# team.net
KiCad netlist of a schematic drawn in EAGLE
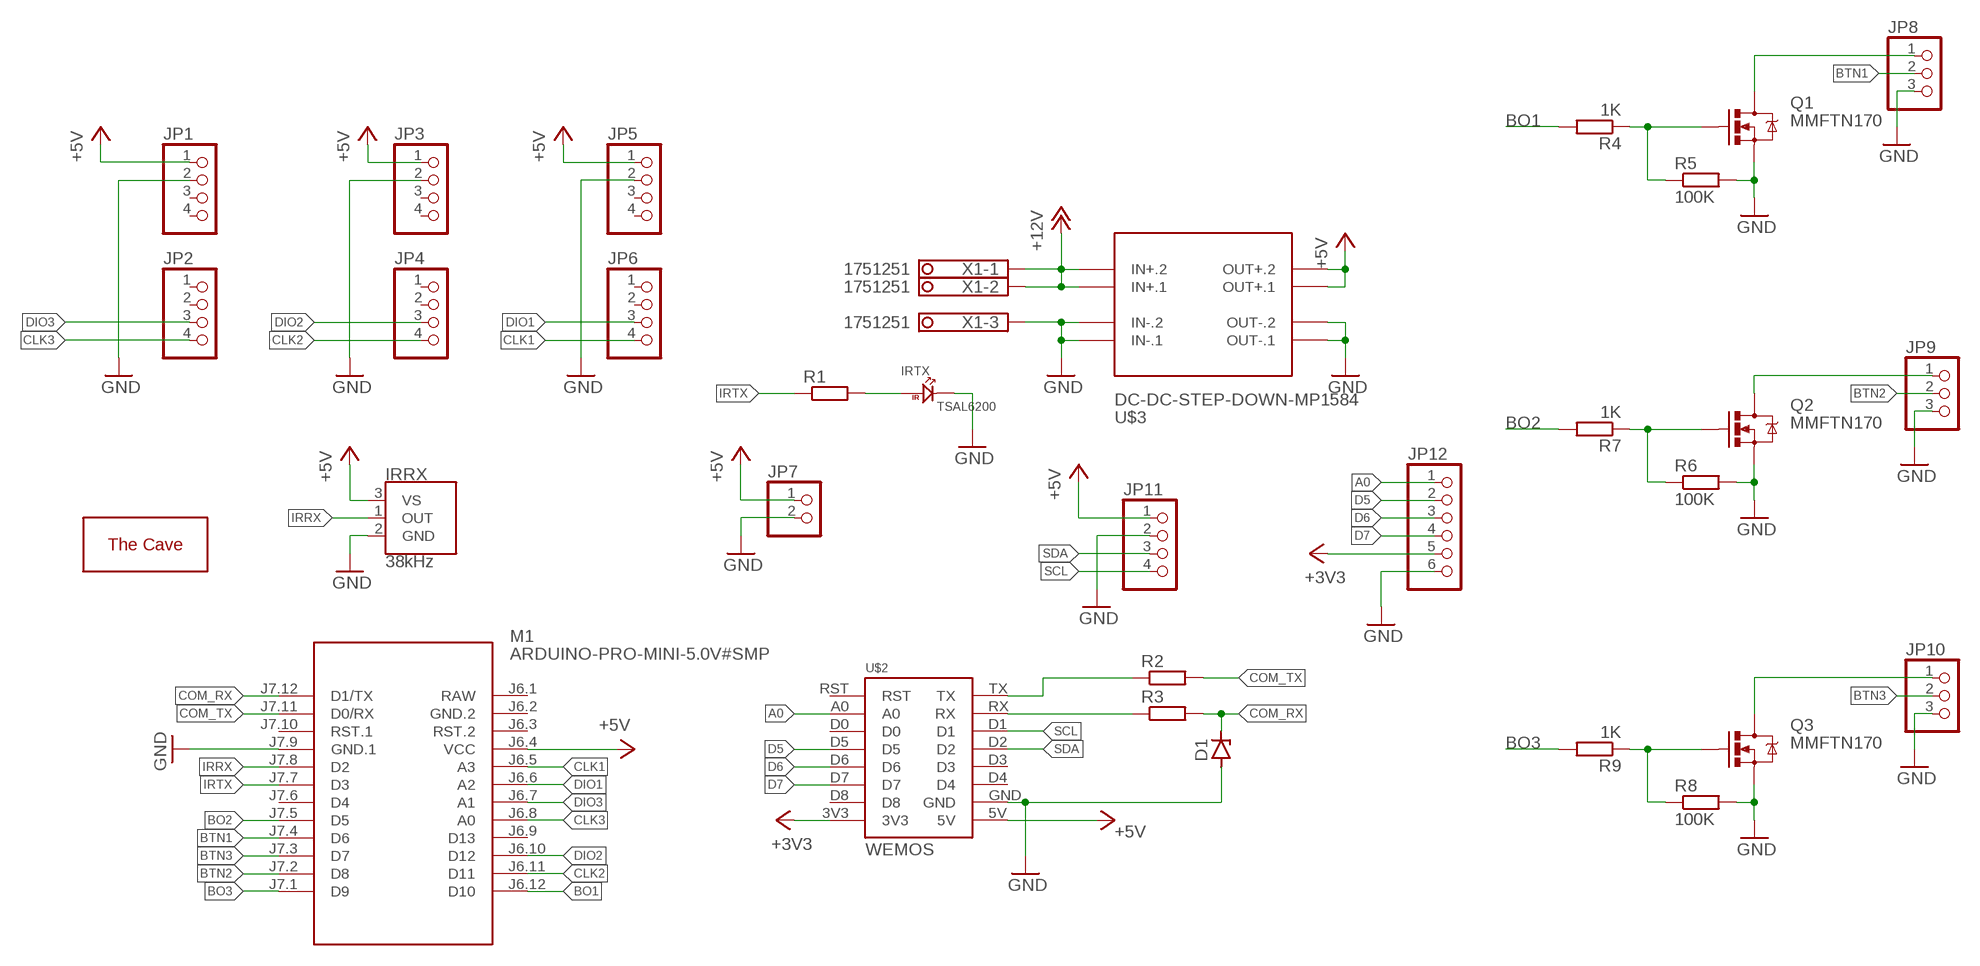
[diagram p0: schematic, sheet 1]

(export (version "E")
  (design (tool "Eeschema 10.0.6"))
  (components
    (comp (ref "D1")
      (value "ZENER-DIODEDO34-7")
      (footprint "eagle-import:DO34Z7")
      (libsource (lib "eagle-import") (part "ZENER-DIODEDO34-7"))
    )
    (comp (ref "IRRX")
      (value "38kHz")
      (footprint "eagle-import:TSOP382")
      (libsource (lib "eagle-import") (part "TSOP38238"))
    )
    (comp (ref "IRTX")
      (value "TSAL6200")
      (footprint "eagle-import:TSAL6200")
      (libsource (lib "eagle-import") (part "TSAL6200"))
    )
    (comp (ref "JP1")
      (value "PINHD-1X4")
      (footprint "eagle-import:1X04")
      (libsource (lib "eagle-import") (part "PINHD-1X4"))
    )
    (comp (ref "JP2")
      (value "PINHD-1X4")
      (footprint "eagle-import:1X04")
      (libsource (lib "eagle-import") (part "PINHD-1X4"))
    )
    (comp (ref "JP3")
      (value "PINHD-1X4")
      (footprint "eagle-import:1X04")
      (libsource (lib "eagle-import") (part "PINHD-1X4"))
    )
    (comp (ref "JP4")
      (value "PINHD-1X4")
      (footprint "eagle-import:1X04")
      (libsource (lib "eagle-import") (part "PINHD-1X4"))
    )
    (comp (ref "JP5")
      (value "PINHD-1X4")
      (footprint "eagle-import:1X04")
      (libsource (lib "eagle-import") (part "PINHD-1X4"))
    )
    (comp (ref "JP6")
      (value "PINHD-1X4")
      (footprint "eagle-import:1X04")
      (libsource (lib "eagle-import") (part "PINHD-1X4"))
    )
    (comp (ref "JP7")
      (value "PINHD-1X2")
      (footprint "eagle-import:1X02")
      (libsource (lib "eagle-import") (part "PINHD-1X2"))
    )
    (comp (ref "JP8")
      (value "PINHD-1X3")
      (footprint "eagle-import:1X03")
      (libsource (lib "eagle-import") (part "PINHD-1X3"))
    )
    (comp (ref "JP9")
      (value "PINHD-1X3")
      (footprint "eagle-import:1X03")
      (libsource (lib "eagle-import") (part "PINHD-1X3"))
    )
    (comp (ref "JP10")
      (value "PINHD-1X3")
      (footprint "eagle-import:1X03")
      (libsource (lib "eagle-import") (part "PINHD-1X3"))
    )
    (comp (ref "JP11")
      (value "PINHD-1X4")
      (footprint "eagle-import:1X04")
      (libsource (lib "eagle-import") (part "PINHD-1X4"))
    )
    (comp (ref "JP12")
      (value "PINHD-1X6")
      (footprint "eagle-import:1X06")
      (libsource (lib "eagle-import") (part "PINHD-1X6"))
    )
    (comp (ref "M1")
      (value "ARDUINO-PRO-MINI-5.0V#SMP")
      (footprint "eagle-import:ARDUINO-PRO-MINI#SMP")
      (libsource (lib "eagle-import") (part "ARDUINO-PRO-MINI-#SMP5.0V"))
    )
    (comp (ref "Q1")
      (value "MMFTN170")
      (footprint "eagle-import:SOT23-3")
      (libsource (lib "eagle-import") (part "MOSFET-NCHANNELAO3404A"))
    )
    (comp (ref "Q2")
      (value "MMFTN170")
      (footprint "eagle-import:SOT23-3")
      (libsource (lib "eagle-import") (part "MOSFET-NCHANNELAO3404A"))
    )
    (comp (ref "Q3")
      (value "MMFTN170")
      (footprint "eagle-import:SOT23-3")
      (libsource (lib "eagle-import") (part "MOSFET-NCHANNELAO3404A"))
    )
    (comp (ref "R1")
      (value "R-EU_0207/7")
      (footprint "eagle-import:0207_7")
      (libsource (lib "eagle-import") (part "rcl_334_R-EU_0207/7"))
    )
    (comp (ref "R2")
      (value "R-EU_0207/7")
      (footprint "eagle-import:0207_7")
      (libsource (lib "eagle-import") (part "rcl_334_R-EU_0207/7"))
    )
    (comp (ref "R3")
      (value "R-EU_0207/7")
      (footprint "eagle-import:0207_7")
      (libsource (lib "eagle-import") (part "rcl_334_R-EU_0207/7"))
    )
    (comp (ref "R4")
      (value "1K")
      (footprint "eagle-import:R0805")
      (libsource (lib "eagle-import") (part "R-EU_R0805"))
    )
    (comp (ref "R5")
      (value "100K")
      (footprint "eagle-import:R0805")
      (libsource (lib "eagle-import") (part "R-EU_R0805"))
    )
    (comp (ref "R6")
      (value "100K")
      (footprint "eagle-import:R0805")
      (libsource (lib "eagle-import") (part "R-EU_R0805"))
    )
    (comp (ref "R7")
      (value "1K")
      (footprint "eagle-import:R0805")
      (libsource (lib "eagle-import") (part "R-EU_R0805"))
    )
    (comp (ref "R8")
      (value "100K")
      (footprint "eagle-import:R0805")
      (libsource (lib "eagle-import") (part "R-EU_R0805"))
    )
    (comp (ref "R9")
      (value "1K")
      (footprint "eagle-import:R0805")
      (libsource (lib "eagle-import") (part "R-EU_R0805"))
    )
    (comp (ref "U$1")
      (value "THECAVE_LOGO_NEW_TOP")
      (footprint "eagle-import:NEW_LOGO_TOP")
      (libsource (lib "eagle-import") (part "THECAVE_LOGO_NEW_TOP"))
    )
    (comp (ref "U$2")
      (value "WEMOS")
      (footprint "eagle-import:WEMOS")
      (libsource (lib "eagle-import") (part "WEMOS"))
    )
    (comp (ref "U$3")
      (value "DC-DC-STEP-DOWN-MP1584")
      (footprint "eagle-import:DC-DC-STEP-DOWN-MP1584")
      (libsource (lib "eagle-import") (part "DC-DC-STEP-DOWN-MP1584"))
    )
    (comp (ref "X1")
      (value "1751251")
      (footprint "eagle-import:1751251")
      (libsource (lib "eagle-import") (part "1751251"))
    )
  )
  (nets
    (net (code "1") (name "+3V3") (class "Default")
      (node (ref "JP12") (pin "5") (pinfunction "5_5") (pintype "passive"))
      (node (ref "U$2") (pin "3V3") (pinfunction "3V3_3V3") (pintype "bidirectional"))
    )
    (net (code "2") (name "+5V") (class "Default")
      (node (ref "IRRX") (pin "3") (pinfunction "VS_3") (pintype "bidirectional"))
      (node (ref "JP1") (pin "1") (pinfunction "1_1") (pintype "passive"))
      (node (ref "JP11") (pin "1") (pinfunction "1_1") (pintype "passive"))
      (node (ref "JP3") (pin "1") (pinfunction "1_1") (pintype "passive"))
      (node (ref "JP5") (pin "1") (pinfunction "1_1") (pintype "passive"))
      (node (ref "JP7") (pin "1") (pinfunction "1_1") (pintype "passive"))
      (node (ref "M1") (pin "J6.4") (pinfunction "VCC_J6.4") (pintype "power_in"))
      (node (ref "U$2") (pin "5V") (pinfunction "5V_5V") (pintype "bidirectional"))
      (node (ref "U$3") (pin "OUT+.1") (pinfunction "OUT+.1_OUT+.1") (pintype "bidirectional"))
      (node (ref "U$3") (pin "OUT+.2") (pinfunction "OUT+.2_OUT+.2") (pintype "bidirectional"))
    )
    (net (code "3") (name "+12V") (class "Default")
      (node (ref "U$3") (pin "IN+.1") (pinfunction "IN+.1_IN+.1") (pintype "bidirectional"))
      (node (ref "U$3") (pin "IN+.2") (pinfunction "IN+.2_IN+.2") (pintype "bidirectional"))
      (node (ref "X1") (pin "1") (pinfunction "K_1") (pintype "passive"))
      (node (ref "X1") (pin "2") (pinfunction "K_2") (pintype "passive"))
    )
    (net (code "4") (name "/GND.2") (class "Default")
      (node (ref "M1") (pin "J6.2") (pinfunction "GND.2_J6.2") (pintype "power_in"))
    )
    (net (code "5") (name "/RAW") (class "Default")
      (node (ref "M1") (pin "J6.1") (pinfunction "RAW_J6.1") (pintype "power_in"))
    )
    (net (code "6") (name "A0") (class "Default")
      (node (ref "JP12") (pin "1") (pinfunction "1_1") (pintype "passive"))
      (node (ref "U$2") (pin "A0") (pinfunction "A0_A0") (pintype "bidirectional"))
    )
    (net (code "7") (name "BO1") (class "Default")
      (node (ref "M1") (pin "J6.12") (pinfunction "D10_J6.12") (pintype "bidirectional"))
      (node (ref "R4") (pin "2") (pinfunction "2_2") (pintype "passive"))
    )
    (net (code "8") (name "BO2") (class "Default")
      (node (ref "M1") (pin "J7.5") (pinfunction "D5_J7.5") (pintype "bidirectional"))
      (node (ref "R7") (pin "2") (pinfunction "2_2") (pintype "passive"))
    )
    (net (code "9") (name "BO3") (class "Default")
      (node (ref "M1") (pin "J7.1") (pinfunction "D9_J7.1") (pintype "bidirectional"))
      (node (ref "R9") (pin "2") (pinfunction "2_2") (pintype "passive"))
    )
    (net (code "10") (name "BTN1") (class "Default")
      (node (ref "JP8") (pin "2") (pinfunction "2_2") (pintype "passive"))
      (node (ref "M1") (pin "J7.4") (pinfunction "D6_J7.4") (pintype "bidirectional"))
    )
    (net (code "11") (name "BTN2") (class "Default")
      (node (ref "JP9") (pin "2") (pinfunction "2_2") (pintype "passive"))
      (node (ref "M1") (pin "J7.2") (pinfunction "D8_J7.2") (pintype "bidirectional"))
    )
    (net (code "12") (name "BTN3") (class "Default")
      (node (ref "JP10") (pin "2") (pinfunction "2_2") (pintype "passive"))
      (node (ref "M1") (pin "J7.3") (pinfunction "D7_J7.3") (pintype "bidirectional"))
    )
    (net (code "13") (name "CLK1") (class "Default")
      (node (ref "JP6") (pin "4") (pinfunction "4_4") (pintype "passive"))
      (node (ref "M1") (pin "J6.5") (pinfunction "A3_J6.5") (pintype "bidirectional"))
    )
    (net (code "14") (name "CLK2") (class "Default")
      (node (ref "JP4") (pin "4") (pinfunction "4_4") (pintype "passive"))
      (node (ref "M1") (pin "J6.11") (pinfunction "D11_J6.11") (pintype "bidirectional"))
    )
    (net (code "15") (name "CLK3") (class "Default")
      (node (ref "JP2") (pin "4") (pinfunction "4_4") (pintype "passive"))
      (node (ref "M1") (pin "J6.8") (pinfunction "A0_J6.8") (pintype "bidirectional"))
    )
    (net (code "16") (name "COM_RX") (class "Default")
      (node (ref "D1") (pin "C") (pinfunction "C_C") (pintype "passive"))
      (node (ref "M1") (pin "J7.12") (pinfunction "D1/TX_J7.12") (pintype "bidirectional"))
      (node (ref "R3") (pin "2") (pinfunction "2_2") (pintype "passive"))
    )
    (net (code "17") (name "COM_TX") (class "Default")
      (node (ref "M1") (pin "J7.11") (pinfunction "D0/RX_J7.11") (pintype "bidirectional"))
      (node (ref "R2") (pin "2") (pinfunction "2_2") (pintype "passive"))
    )
    (net (code "18") (name "D5") (class "Default")
      (node (ref "JP12") (pin "2") (pinfunction "2_2") (pintype "passive"))
      (node (ref "U$2") (pin "D5") (pinfunction "D5_D5") (pintype "bidirectional"))
    )
    (net (code "19") (name "D6") (class "Default")
      (node (ref "JP12") (pin "3") (pinfunction "3_3") (pintype "passive"))
      (node (ref "U$2") (pin "D6") (pinfunction "D6_D6") (pintype "bidirectional"))
    )
    (net (code "20") (name "D7") (class "Default")
      (node (ref "JP12") (pin "4") (pinfunction "4_4") (pintype "passive"))
      (node (ref "U$2") (pin "D7") (pinfunction "D7_D7") (pintype "bidirectional"))
    )
    (net (code "21") (name "DIO1") (class "Default")
      (node (ref "JP6") (pin "3") (pinfunction "3_3") (pintype "passive"))
      (node (ref "M1") (pin "J6.6") (pinfunction "A2_J6.6") (pintype "bidirectional"))
    )
    (net (code "22") (name "DIO2") (class "Default")
      (node (ref "JP4") (pin "3") (pinfunction "3_3") (pintype "passive"))
      (node (ref "M1") (pin "J6.10") (pinfunction "D12_J6.10") (pintype "bidirectional"))
    )
    (net (code "23") (name "DIO3") (class "Default")
      (node (ref "JP2") (pin "3") (pinfunction "3_3") (pintype "passive"))
      (node (ref "M1") (pin "J6.7") (pinfunction "A1_J6.7") (pintype "bidirectional"))
    )
    (net (code "24") (name "GND") (class "Default")
      (node (ref "D1") (pin "A") (pinfunction "A_A") (pintype "passive"))
      (node (ref "IRRX") (pin "2") (pinfunction "GND_2") (pintype "bidirectional"))
      (node (ref "IRTX") (pin "N") (pinfunction "N_N") (pintype "bidirectional"))
      (node (ref "JP1") (pin "2") (pinfunction "2_2") (pintype "passive"))
      (node (ref "JP10") (pin "3") (pinfunction "3_3") (pintype "passive"))
      (node (ref "JP11") (pin "2") (pinfunction "2_2") (pintype "passive"))
      (node (ref "JP12") (pin "6") (pinfunction "6_6") (pintype "passive"))
      (node (ref "JP3") (pin "2") (pinfunction "2_2") (pintype "passive"))
      (node (ref "JP5") (pin "2") (pinfunction "2_2") (pintype "passive"))
      (node (ref "JP7") (pin "2") (pinfunction "2_2") (pintype "passive"))
      (node (ref "JP8") (pin "3") (pinfunction "3_3") (pintype "passive"))
      (node (ref "JP9") (pin "3") (pinfunction "3_3") (pintype "passive"))
      (node (ref "M1") (pin "J7.9") (pinfunction "GND.1_J7.9") (pintype "power_in"))
      (node (ref "Q1") (pin "2") (pinfunction "S_2") (pintype "passive"))
      (node (ref "Q2") (pin "2") (pinfunction "S_2") (pintype "passive"))
      (node (ref "Q3") (pin "2") (pinfunction "S_2") (pintype "passive"))
      (node (ref "R5") (pin "2") (pinfunction "2_2") (pintype "passive"))
      (node (ref "R6") (pin "2") (pinfunction "2_2") (pintype "passive"))
      (node (ref "R8") (pin "2") (pinfunction "2_2") (pintype "passive"))
      (node (ref "U$2") (pin "GND") (pinfunction "GND_GND") (pintype "bidirectional"))
      (node (ref "U$3") (pin "IN-.1") (pinfunction "IN-.1_IN-.1") (pintype "bidirectional"))
      (node (ref "U$3") (pin "IN-.2") (pinfunction "IN-.2_IN-.2") (pintype "bidirectional"))
      (node (ref "U$3") (pin "OUT-.1") (pinfunction "OUT-.1_OUT-.1") (pintype "bidirectional"))
      (node (ref "U$3") (pin "OUT-.2") (pinfunction "OUT-.2_OUT-.2") (pintype "bidirectional"))
      (node (ref "X1") (pin "3") (pinfunction "K_3") (pintype "passive"))
    )
    (net (code "25") (name "IRRX") (class "Default")
      (node (ref "IRRX") (pin "1") (pinfunction "OUT_1") (pintype "bidirectional"))
      (node (ref "M1") (pin "J7.8") (pinfunction "D2_J7.8") (pintype "bidirectional"))
    )
    (net (code "26") (name "IRTX") (class "Default")
      (node (ref "M1") (pin "J7.7") (pinfunction "D3_J7.7") (pintype "bidirectional"))
      (node (ref "R1") (pin "1") (pinfunction "1_1") (pintype "passive"))
    )
    (net (code "27") (name "Net-(IRTX-PadP)") (class "Default")
      (node (ref "IRTX") (pin "P") (pinfunction "P_P") (pintype "bidirectional"))
      (node (ref "R1") (pin "2") (pinfunction "2_2") (pintype "passive"))
    )
    (net (code "28") (name "Net-(Q1-D)") (class "Default")
      (node (ref "JP8") (pin "1") (pinfunction "1_1") (pintype "passive"))
      (node (ref "Q1") (pin "3") (pinfunction "D_3") (pintype "passive"))
    )
    (net (code "29") (name "Net-(Q1-G)") (class "Default")
      (node (ref "Q1") (pin "1") (pinfunction "G_1") (pintype "passive"))
      (node (ref "R4") (pin "1") (pinfunction "1_1") (pintype "passive"))
      (node (ref "R5") (pin "1") (pinfunction "1_1") (pintype "passive"))
    )
    (net (code "30") (name "Net-(Q2-D)") (class "Default")
      (node (ref "JP9") (pin "1") (pinfunction "1_1") (pintype "passive"))
      (node (ref "Q2") (pin "3") (pinfunction "D_3") (pintype "passive"))
    )
    (net (code "31") (name "Net-(Q2-G)") (class "Default")
      (node (ref "Q2") (pin "1") (pinfunction "G_1") (pintype "passive"))
      (node (ref "R6") (pin "1") (pinfunction "1_1") (pintype "passive"))
      (node (ref "R7") (pin "1") (pinfunction "1_1") (pintype "passive"))
    )
    (net (code "32") (name "Net-(Q3-D)") (class "Default")
      (node (ref "JP10") (pin "1") (pinfunction "1_1") (pintype "passive"))
      (node (ref "Q3") (pin "3") (pinfunction "D_3") (pintype "passive"))
    )
    (net (code "33") (name "Net-(Q3-G)") (class "Default")
      (node (ref "Q3") (pin "1") (pinfunction "G_1") (pintype "passive"))
      (node (ref "R8") (pin "1") (pinfunction "1_1") (pintype "passive"))
      (node (ref "R9") (pin "1") (pinfunction "1_1") (pintype "passive"))
    )
    (net (code "34") (name "Net-(R2-Pad1)") (class "Default")
      (node (ref "R2") (pin "1") (pinfunction "1_1") (pintype "passive"))
      (node (ref "U$2") (pin "TX") (pinfunction "TX_TX") (pintype "bidirectional"))
    )
    (net (code "35") (name "Net-(R3-Pad1)") (class "Default")
      (node (ref "R3") (pin "1") (pinfunction "1_1") (pintype "passive"))
      (node (ref "U$2") (pin "RX") (pinfunction "RX_RX") (pintype "bidirectional"))
    )
    (net (code "36") (name "SCL") (class "Default")
      (node (ref "JP11") (pin "4") (pinfunction "4_4") (pintype "passive"))
      (node (ref "U$2") (pin "D1") (pinfunction "D1_D1") (pintype "bidirectional"))
    )
    (net (code "37") (name "SDA") (class "Default")
      (node (ref "JP11") (pin "3") (pinfunction "3_3") (pintype "passive"))
      (node (ref "U$2") (pin "D2") (pinfunction "D2_D2") (pintype "bidirectional"))
    )
    (net (code "38") (name "unconnected-(JP1-Pad3)") (class "Default")
      (node (ref "JP1") (pin "3") (pinfunction "3_3") (pintype "passive"))
    )
    (net (code "39") (name "unconnected-(JP1-Pad4)") (class "Default")
      (node (ref "JP1") (pin "4") (pinfunction "4_4") (pintype "passive"))
    )
    (net (code "40") (name "unconnected-(JP2-Pad1)") (class "Default")
      (node (ref "JP2") (pin "1") (pinfunction "1_1") (pintype "passive"))
    )
    (net (code "41") (name "unconnected-(JP2-Pad2)") (class "Default")
      (node (ref "JP2") (pin "2") (pinfunction "2_2") (pintype "passive"))
    )
    (net (code "42") (name "unconnected-(JP3-Pad3)") (class "Default")
      (node (ref "JP3") (pin "3") (pinfunction "3_3") (pintype "passive"))
    )
    (net (code "43") (name "unconnected-(JP3-Pad4)") (class "Default")
      (node (ref "JP3") (pin "4") (pinfunction "4_4") (pintype "passive"))
    )
    (net (code "44") (name "unconnected-(JP4-Pad1)") (class "Default")
      (node (ref "JP4") (pin "1") (pinfunction "1_1") (pintype "passive"))
    )
    (net (code "45") (name "unconnected-(JP4-Pad2)") (class "Default")
      (node (ref "JP4") (pin "2") (pinfunction "2_2") (pintype "passive"))
    )
    (net (code "46") (name "unconnected-(JP5-Pad3)") (class "Default")
      (node (ref "JP5") (pin "3") (pinfunction "3_3") (pintype "passive"))
    )
    (net (code "47") (name "unconnected-(JP5-Pad4)") (class "Default")
      (node (ref "JP5") (pin "4") (pinfunction "4_4") (pintype "passive"))
    )
    (net (code "48") (name "unconnected-(JP6-Pad1)") (class "Default")
      (node (ref "JP6") (pin "1") (pinfunction "1_1") (pintype "passive"))
    )
    (net (code "49") (name "unconnected-(JP6-Pad2)") (class "Default")
      (node (ref "JP6") (pin "2") (pinfunction "2_2") (pintype "passive"))
    )
    (net (code "50") (name "unconnected-(M1-D4-PadJ7.6)") (class "Default")
      (node (ref "M1") (pin "J7.6") (pinfunction "D4_J7.6") (pintype "bidirectional"))
    )
    (net (code "51") (name "unconnected-(M1-D13-PadJ6.9)") (class "Default")
      (node (ref "M1") (pin "J6.9") (pinfunction "D13_J6.9") (pintype "bidirectional"))
    )
    (net (code "52") (name "unconnected-(M1-RST.1-PadJ7.10)") (class "Default")
      (node (ref "M1") (pin "J7.10") (pinfunction "RST.1_J7.10") (pintype "bidirectional"))
    )
    (net (code "53") (name "unconnected-(M1-RST.2-PadJ6.3)") (class "Default")
      (node (ref "M1") (pin "J6.3") (pinfunction "RST.2_J6.3") (pintype "bidirectional"))
    )
    (net (code "54") (name "unconnected-(U$2-PadD0)") (class "Default")
      (node (ref "U$2") (pin "D0") (pinfunction "D0_D0") (pintype "bidirectional"))
    )
    (net (code "55") (name "unconnected-(U$2-PadD3)") (class "Default")
      (node (ref "U$2") (pin "D3") (pinfunction "D3_D3") (pintype "bidirectional"))
    )
    (net (code "56") (name "unconnected-(U$2-PadD4)") (class "Default")
      (node (ref "U$2") (pin "D4") (pinfunction "D4_D4") (pintype "bidirectional"))
    )
    (net (code "57") (name "unconnected-(U$2-PadD8)") (class "Default")
      (node (ref "U$2") (pin "D8") (pinfunction "D8_D8") (pintype "bidirectional"))
    )
    (net (code "58") (name "unconnected-(U$2-PadRST)") (class "Default")
      (node (ref "U$2") (pin "RST") (pinfunction "RST_RST") (pintype "bidirectional"))
    )
  )
)
